# 03b3_USB_HUB.net
KiCad netlist of a schematic drawn in Altium Designer
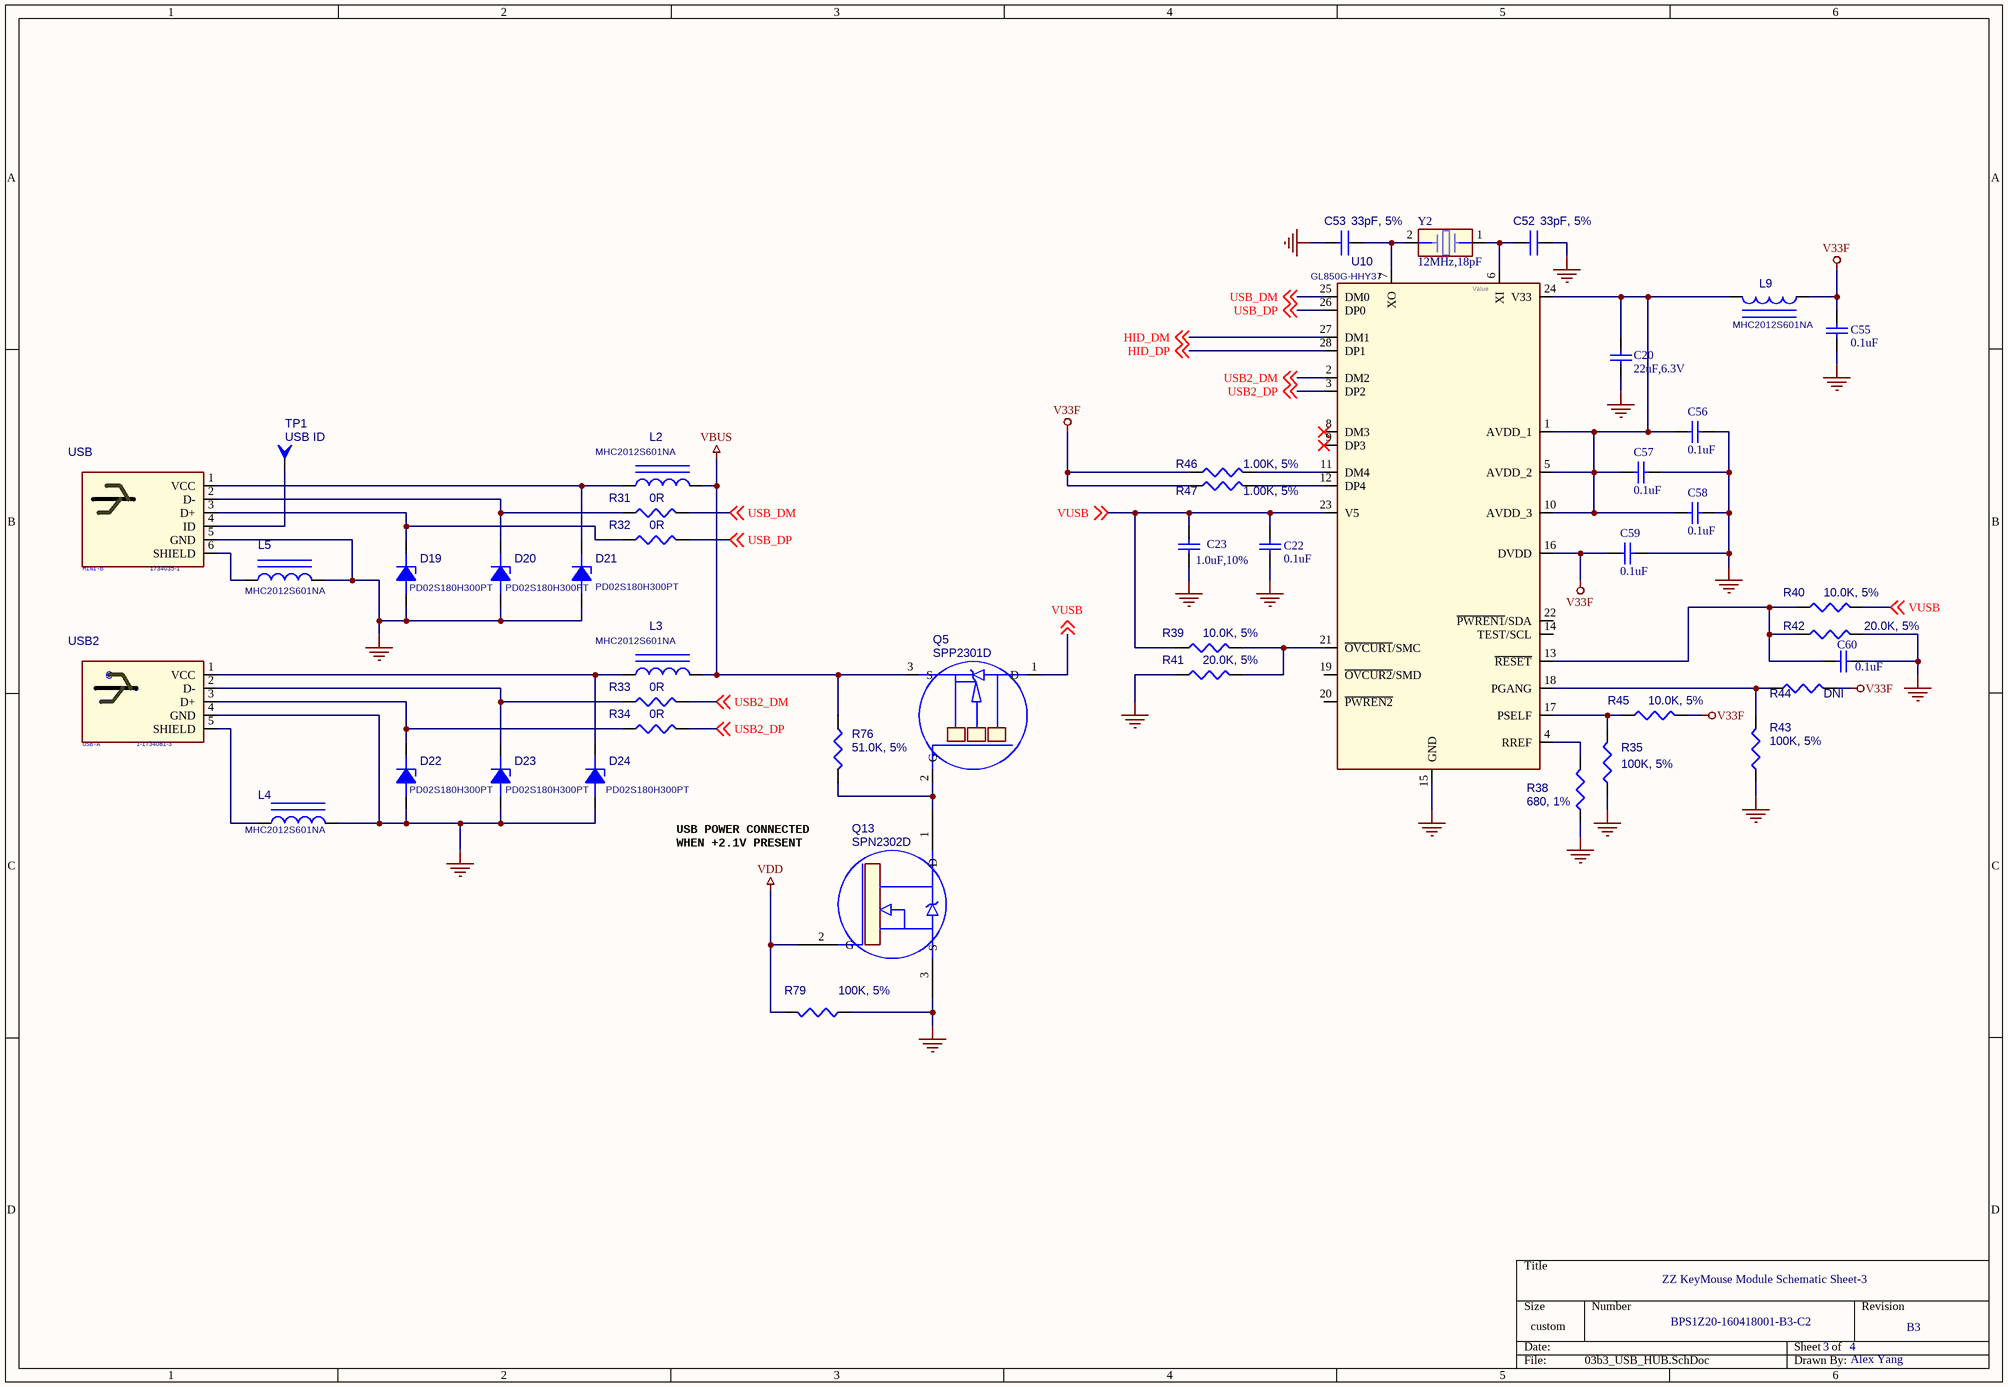
[diagram p0: 03b3_USB_HUB.SchDoc]

(export (version "E")
  (design (tool "Eeschema 10.0.6"))
  (components
    (comp (ref "C20")
      (value "22uF,6.3V")
      (footprint "MIN0805")
      (description "Capacitor")
      (libsource (lib "Miscellaneous Devices") (part "Cap"))
    )
    (comp (ref "C22")
      (value "0.1uF")
      (footprint "0603")
      (description "Capacitor")
      (libsource (lib "Miscellaneous Devices") (part "Cap"))
    )
    (comp (ref "C23")
      (value "1.0uF,10%")
      (footprint "0603")
      (description "Capacitor")
      (libsource (lib "Miscellaneous Devices") (part "Cap"))
    )
    (comp (ref "C52") (value "33pF, 5%") (footprint "0402") (libsource (lib "*") (part "CAPACITOR NON-POL")))
    (comp (ref "C53") (value "33pF, 5%") (footprint "0402") (libsource (lib "*") (part "CAPACITOR NON-POL")))
    (comp (ref "C55")
      (value "0.1uF")
      (footprint "0603")
      (description "Capacitor")
      (libsource (lib "Miscellaneous Devices") (part "Cap"))
    )
    (comp (ref "C56")
      (value "0.1uF")
      (footprint "0603")
      (description "Capacitor")
      (libsource (lib "Miscellaneous Devices") (part "Cap"))
    )
    (comp (ref "C57")
      (value "0.1uF")
      (footprint "0603")
      (description "Capacitor")
      (libsource (lib "Miscellaneous Devices") (part "Cap"))
    )
    (comp (ref "C58")
      (value "0.1uF")
      (footprint "0603")
      (description "Capacitor")
      (libsource (lib "Miscellaneous Devices") (part "Cap"))
    )
    (comp (ref "C59")
      (value "0.1uF")
      (footprint "0603")
      (description "Capacitor")
      (libsource (lib "Miscellaneous Devices") (part "Cap"))
    )
    (comp (ref "C60")
      (value "0.1uF")
      (footprint "0603")
      (description "Capacitor")
      (libsource (lib "Miscellaneous Devices") (part "Cap"))
    )
    (comp (ref "D19")
      (value "PD02S180H300PT")
      (footprint "ON_SEMI_ESD9L_SOD923")
      (libsource (lib "R MAIN") (part "DIODE BREAKDOWN"))
    )
    (comp (ref "D20")
      (value "PD02S180H300PT")
      (footprint "ON_SEMI_ESD9L_SOD923")
      (libsource (lib "R MAIN") (part "DIODE BREAKDOWN"))
    )
    (comp (ref "D21")
      (value "PD02S180H300PT")
      (footprint "ON_SEMI_ESD9L_SOD923")
      (libsource (lib "R MAIN") (part "DIODE BREAKDOWN"))
    )
    (comp (ref "D22")
      (value "PD02S180H300PT")
      (footprint "ON_SEMI_ESD9L_SOD923")
      (libsource (lib "R MAIN") (part "DIODE BREAKDOWN"))
    )
    (comp (ref "D23")
      (value "PD02S180H300PT")
      (footprint "ON_SEMI_ESD9L_SOD923")
      (libsource (lib "R MAIN") (part "DIODE BREAKDOWN"))
    )
    (comp (ref "D24")
      (value "PD02S180H300PT")
      (footprint "ON_SEMI_ESD9L_SOD923")
      (libsource (lib "R MAIN") (part "DIODE BREAKDOWN"))
    )
    (comp (ref "L2")
      (value "MHC2012S601NA")
      (footprint "RESC2012X70")
      (libsource (lib "*") (part "INDUCTOR IRON"))
    )
    (comp (ref "L3")
      (value "MHC2012S601NA")
      (footprint "RESC2012X70")
      (libsource (lib "*") (part "INDUCTOR IRON"))
    )
    (comp (ref "L4")
      (value "MHC2012S601NA")
      (footprint "RESC2012X70")
      (libsource (lib "*") (part "INDUCTOR IRON"))
    )
    (comp (ref "L5")
      (value "MHC2012S601NA")
      (footprint "RESC2012X70")
      (libsource (lib "*") (part "INDUCTOR IRON"))
    )
    (comp (ref "L9")
      (value "MHC2012S601NA")
      (footprint "RESC2012X70")
      (libsource (lib "*") (part "INDUCTOR IRON"))
    )
    (comp (ref "Q5") (value "SPP2301D") (footprint "SOT23") (libsource (lib "R MAIN") (part "AO3435")))
    (comp (ref "Q13") (value "SPN2302D") (footprint "SOT23") (libsource (lib "L MAIN") (part "AO3416")))
    (comp (ref "R31") (value "0R") (footprint "0402") (libsource (lib "*") (part "R")))
    (comp (ref "R32") (value "0R") (footprint "0402") (libsource (lib "*") (part "R")))
    (comp (ref "R33") (value "0R") (footprint "0402") (libsource (lib "*") (part "R")))
    (comp (ref "R34") (value "0R") (footprint "0402") (libsource (lib "*") (part "R")))
    (comp (ref "R35") (value "100K, 5%") (footprint "0402") (libsource (lib "*") (part "R")))
    (comp (ref "R38") (value "680, 1%") (footprint "0402") (libsource (lib "*") (part "R")))
    (comp (ref "R39") (value "10.0K, 5%") (footprint "0402") (libsource (lib "*") (part "R")))
    (comp (ref "R40") (value "10.0K, 5%") (footprint "0402") (libsource (lib "*") (part "R")))
    (comp (ref "R41") (value "20.0K, 5%") (footprint "0402") (libsource (lib "*") (part "R")))
    (comp (ref "R42") (value "20.0K, 5%") (footprint "0402") (libsource (lib "*") (part "R")))
    (comp (ref "R43") (value "100K, 5%") (footprint "0402") (libsource (lib "*") (part "R")))
    (comp (ref "R44") (value "DNI") (footprint "0402") (libsource (lib "*") (part "R")))
    (comp (ref "R45") (value "10.0K, 5%") (footprint "0402") (libsource (lib "*") (part "R")))
    (comp (ref "R46") (value "1.00K, 5%") (footprint "0402") (libsource (lib "*") (part "R")))
    (comp (ref "R47") (value "1.00K, 5%") (footprint "0402") (libsource (lib "*") (part "R")))
    (comp (ref "R76") (value "51.0K, 5%") (footprint "0402") (libsource (lib "*") (part "R")))
    (comp (ref "R79") (value "100K, 5%") (footprint "0402") (libsource (lib "*") (part "R")))
    (comp (ref "TP1") (value "USB ID") (footprint "TP1.5MM") (libsource (lib "*") (part "T POINT A")))
    (comp (ref "U10")
      (value "GL850G-HHY37")
      (footprint "SSOP28")
      (libsource (lib "*") (part "GL850G-HHY37_0"))
    )
    (comp (ref "USB")
      (value "1734035-1")
      (footprint "MINI-B_TE_1734035-1")
      (libsource (lib "L MAIN") (part "USB-MINI-B_0"))
    )
    (comp (ref "USB2")
      (value "1-1734081-3")
      (footprint "TE_1-1734081-3")
      (libsource (lib "L MAIN") (part "USB-A_1"))
    )
    (comp (ref "Y2")
      (value "12MHz,18pF")
      (footprint "TXC_HC-49S")
      (description "XTAL_CS10-25.000,18PF")
      (fields (field (name "FREQUENCY") "Value"))
      (libsource (lib "L MAIN_Library") (part "XTAL-25MHz_0"))
    )
  )
  (nets
    (net (code "1") (name "GND") (class "Default")
      (node (ref "C20") (pin "2") (pinfunction "2_2") (pintype "passive"))
      (node (ref "C22") (pin "1") (pinfunction "1_1") (pintype "passive"))
      (node (ref "C23") (pin "1") (pinfunction "1_1") (pintype "passive"))
      (node (ref "C52") (pin "1") (pinfunction "1_1") (pintype "passive"))
      (node (ref "C53") (pin "2") (pinfunction "2_2") (pintype "passive"))
      (node (ref "C55") (pin "1") (pinfunction "1_1") (pintype "passive"))
      (node (ref "C56") (pin "2") (pinfunction "2_2") (pintype "passive"))
      (node (ref "C57") (pin "2") (pinfunction "2_2") (pintype "passive"))
      (node (ref "C58") (pin "2") (pinfunction "2_2") (pintype "passive"))
      (node (ref "C59") (pin "2") (pinfunction "2_2") (pintype "passive"))
      (node (ref "C60") (pin "1") (pinfunction "1_1") (pintype "passive"))
      (node (ref "D19") (pin "A") (pinfunction "ANODE_A") (pintype "passive"))
      (node (ref "D20") (pin "A") (pinfunction "ANODE_A") (pintype "passive"))
      (node (ref "D21") (pin "A") (pinfunction "ANODE_A") (pintype "passive"))
      (node (ref "D22") (pin "A") (pinfunction "ANODE_A") (pintype "passive"))
      (node (ref "D23") (pin "A") (pinfunction "ANODE_A") (pintype "passive"))
      (node (ref "D24") (pin "A") (pinfunction "ANODE_A") (pintype "passive"))
      (node (ref "L4") (pin "2") (pinfunction "2_2") (pintype "passive"))
      (node (ref "L5") (pin "2") (pinfunction "2_2") (pintype "passive"))
      (node (ref "Q13") (pin "3") (pinfunction "S_3") (pintype "passive"))
      (node (ref "R35") (pin "1") (pinfunction "1_1") (pintype "passive"))
      (node (ref "R38") (pin "2") (pinfunction "2_2") (pintype "passive"))
      (node (ref "R41") (pin "1") (pinfunction "1_1") (pintype "passive"))
      (node (ref "R42") (pin "2") (pinfunction "2_2") (pintype "passive"))
      (node (ref "R43") (pin "1") (pinfunction "1_1") (pintype "passive"))
      (node (ref "R79") (pin "1") (pinfunction "1_1") (pintype "passive"))
      (node (ref "U10") (pin "15") (pinfunction "GND_15") (pintype "passive"))
      (node (ref "USB") (pin "5") (pinfunction "GND_5") (pintype "passive"))
      (node (ref "USB2") (pin "4") (pinfunction "GND_4") (pintype "passive"))
    )
    (net (code "2") (name "HID_DM") (class "Default")
      (node (ref "U10") (pin "27") (pinfunction "DM1_27") (pintype "passive"))
    )
    (net (code "3") (name "HID_DP") (class "Default")
      (node (ref "U10") (pin "28") (pinfunction "DP1_28") (pintype "passive"))
    )
    (net (code "4") (name "Net-(D19-CATHODE)") (class "Default")
      (node (ref "D19") (pin "K") (pinfunction "CATHODE_K") (pintype "passive"))
      (node (ref "R32") (pin "1") (pinfunction "1_1") (pintype "passive"))
      (node (ref "USB") (pin "3") (pinfunction "D+_3") (pintype "passive"))
    )
    (net (code "5") (name "Net-(D20-CATHODE)") (class "Default")
      (node (ref "D20") (pin "K") (pinfunction "CATHODE_K") (pintype "passive"))
      (node (ref "R31") (pin "1") (pinfunction "1_1") (pintype "passive"))
      (node (ref "USB") (pin "2") (pinfunction "D-_2") (pintype "passive"))
    )
    (net (code "6") (name "Net-(D21-CATHODE)") (class "Default")
      (node (ref "D21") (pin "K") (pinfunction "CATHODE_K") (pintype "passive"))
      (node (ref "L2") (pin "1") (pinfunction "1_1") (pintype "passive"))
      (node (ref "USB") (pin "1") (pinfunction "VCC_1") (pintype "passive"))
    )
    (net (code "7") (name "Net-(D22-CATHODE)") (class "Default")
      (node (ref "D22") (pin "K") (pinfunction "CATHODE_K") (pintype "passive"))
      (node (ref "R34") (pin "1") (pinfunction "1_1") (pintype "passive"))
      (node (ref "USB2") (pin "3") (pinfunction "D+_3") (pintype "passive"))
    )
    (net (code "8") (name "Net-(D23-CATHODE)") (class "Default")
      (node (ref "D23") (pin "K") (pinfunction "CATHODE_K") (pintype "passive"))
      (node (ref "R33") (pin "1") (pinfunction "1_1") (pintype "passive"))
      (node (ref "USB2") (pin "2") (pinfunction "D-_2") (pintype "passive"))
    )
    (net (code "9") (name "Net-(D24-CATHODE)") (class "Default")
      (node (ref "D24") (pin "K") (pinfunction "CATHODE_K") (pintype "passive"))
      (node (ref "L3") (pin "1") (pinfunction "1_1") (pintype "passive"))
      (node (ref "USB2") (pin "1") (pinfunction "VCC_1") (pintype "passive"))
    )
    (net (code "10") (name "Net-(Q13-D)") (class "Default")
      (node (ref "Q13") (pin "1") (pinfunction "D_1") (pintype "passive"))
      (node (ref "Q5") (pin "2") (pinfunction "G_2") (pintype "passive"))
      (node (ref "R76") (pin "2") (pinfunction "2_2") (pintype "passive"))
    )
    (net (code "11") (name "Net-(TP1-TP)") (class "Default")
      (node (ref "TP1") (pin "1") (pinfunction "TP_1") (pintype "passive"))
      (node (ref "USB") (pin "4") (pinfunction "ID_4") (pintype "passive"))
    )
    (net (code "12") (name "Net-(U10-AVDD_1)") (class "Default")
      (node (ref "C20") (pin "1") (pinfunction "1_1") (pintype "passive"))
      (node (ref "C56") (pin "1") (pinfunction "1_1") (pintype "passive"))
      (node (ref "C57") (pin "1") (pinfunction "1_1") (pintype "passive"))
      (node (ref "C58") (pin "1") (pinfunction "1_1") (pintype "passive"))
      (node (ref "L9") (pin "2") (pinfunction "2_2") (pintype "passive"))
      (node (ref "U10") (pin "1") (pinfunction "AVDD_1_1") (pintype "passive"))
      (node (ref "U10") (pin "10") (pinfunction "AVDD_3_10") (pintype "passive"))
      (node (ref "U10") (pin "24") (pinfunction "V33_24") (pintype "passive"))
      (node (ref "U10") (pin "5") (pinfunction "AVDD_2_5") (pintype "passive"))
    )
    (net (code "13") (name "Net-(U10-DM4)") (class "Default")
      (node (ref "R46") (pin "2") (pinfunction "2_2") (pintype "passive"))
      (node (ref "U10") (pin "11") (pinfunction "DM4_11") (pintype "passive"))
    )
    (net (code "14") (name "Net-(U10-DP4)") (class "Default")
      (node (ref "R47") (pin "2") (pinfunction "2_2") (pintype "passive"))
      (node (ref "U10") (pin "12") (pinfunction "DP4_12") (pintype "passive"))
    )
    (net (code "15") (name "Net-(U10-PGANG)") (class "Default")
      (node (ref "R43") (pin "2") (pinfunction "2_2") (pintype "passive"))
      (node (ref "R44") (pin "1") (pinfunction "1_1") (pintype "passive"))
      (node (ref "U10") (pin "18") (pinfunction "PGANG_18") (pintype "passive"))
    )
    (net (code "16") (name "Net-(U10-PSELF)") (class "Default")
      (node (ref "R35") (pin "2") (pinfunction "2_2") (pintype "passive"))
      (node (ref "R45") (pin "1") (pinfunction "1_1") (pintype "passive"))
      (node (ref "U10") (pin "17") (pinfunction "PSELF_17") (pintype "passive"))
    )
    (net (code "17") (name "Net-(U10-RREF)") (class "Default")
      (node (ref "R38") (pin "1") (pinfunction "1_1") (pintype "passive"))
      (node (ref "U10") (pin "4") (pinfunction "RREF_4") (pintype "passive"))
    )
    (net (code "18") (name "Net-(U10-XI)") (class "Default")
      (node (ref "C52") (pin "2") (pinfunction "2_2") (pintype "passive"))
      (node (ref "U10") (pin "6") (pinfunction "XI_6") (pintype "passive"))
      (node (ref "Y2") (pin "1") (pinfunction "1_1") (pintype "passive"))
    )
    (net (code "19") (name "Net-(U10-XO)") (class "Default")
      (node (ref "C53") (pin "1") (pinfunction "1_1") (pintype "passive"))
      (node (ref "U10") (pin "7") (pinfunction "XO_7") (pintype "passive"))
      (node (ref "Y2") (pin "2") (pinfunction "2_2") (pintype "passive"))
    )
    (net (code "20") (name "Net-(U10-~{OVCUR1}{slash}SMC)") (class "Default")
      (node (ref "R39") (pin "2") (pinfunction "2_2") (pintype "passive"))
      (node (ref "R41") (pin "2") (pinfunction "2_2") (pintype "passive"))
      (node (ref "U10") (pin "21") (pinfunction "~{OVCUR1}/SMC_21") (pintype "passive"))
    )
    (net (code "21") (name "Net-(U10-~{RESET})") (class "Default")
      (node (ref "C60") (pin "2") (pinfunction "2_2") (pintype "passive"))
      (node (ref "R40") (pin "1") (pinfunction "1_1") (pintype "passive"))
      (node (ref "R42") (pin "1") (pinfunction "1_1") (pintype "passive"))
      (node (ref "U10") (pin "13") (pinfunction "~{RESET}_13") (pintype "passive"))
    )
    (net (code "22") (name "Net-(USB-SHIELD)") (class "Default")
      (node (ref "L5") (pin "1") (pinfunction "1_1") (pintype "passive"))
      (node (ref "USB") (pin "6") (pinfunction "SHIELD_6") (pintype "passive"))
    )
    (net (code "23") (name "Net-(USB2-SHIELD)") (class "Default")
      (node (ref "L4") (pin "1") (pinfunction "1_1") (pintype "passive"))
      (node (ref "USB2") (pin "5") (pinfunction "SHIELD_5") (pintype "passive"))
    )
    (net (code "24") (name "USB2_DM") (class "Default")
      (node (ref "R33") (pin "2") (pinfunction "2_2") (pintype "passive"))
      (node (ref "U10") (pin "2") (pinfunction "DM2_2") (pintype "passive"))
    )
    (net (code "25") (name "USB2_DP") (class "Default")
      (node (ref "R34") (pin "2") (pinfunction "2_2") (pintype "passive"))
      (node (ref "U10") (pin "3") (pinfunction "DP2_3") (pintype "passive"))
    )
    (net (code "26") (name "USB_DM") (class "Default")
      (node (ref "R31") (pin "2") (pinfunction "2_2") (pintype "passive"))
      (node (ref "U10") (pin "25") (pinfunction "DM0_25") (pintype "passive"))
    )
    (net (code "27") (name "USB_DP") (class "Default")
      (node (ref "R32") (pin "2") (pinfunction "2_2") (pintype "passive"))
      (node (ref "U10") (pin "26") (pinfunction "DP0_26") (pintype "passive"))
    )
    (net (code "28") (name "V33F") (class "Default")
      (node (ref "C55") (pin "2") (pinfunction "2_2") (pintype "passive"))
      (node (ref "C59") (pin "1") (pinfunction "1_1") (pintype "passive"))
      (node (ref "L9") (pin "1") (pinfunction "1_1") (pintype "passive"))
      (node (ref "R44") (pin "2") (pinfunction "2_2") (pintype "passive"))
      (node (ref "R45") (pin "2") (pinfunction "2_2") (pintype "passive"))
      (node (ref "R46") (pin "1") (pinfunction "1_1") (pintype "passive"))
      (node (ref "R47") (pin "1") (pinfunction "1_1") (pintype "passive"))
      (node (ref "U10") (pin "16") (pinfunction "DVDD_16") (pintype "passive"))
    )
    (net (code "29") (name "VBUS") (class "Default")
      (node (ref "L2") (pin "2") (pinfunction "2_2") (pintype "passive"))
      (node (ref "L3") (pin "2") (pinfunction "2_2") (pintype "passive"))
      (node (ref "Q5") (pin "3") (pinfunction "S_3") (pintype "passive"))
      (node (ref "R76") (pin "1") (pinfunction "1_1") (pintype "passive"))
    )
    (net (code "30") (name "VDD") (class "Default")
      (node (ref "Q13") (pin "2") (pinfunction "G_2") (pintype "passive"))
      (node (ref "R79") (pin "2") (pinfunction "2_2") (pintype "passive"))
    )
    (net (code "31") (name "VUSB") (class "Default")
      (node (ref "C22") (pin "2") (pinfunction "2_2") (pintype "passive"))
      (node (ref "C23") (pin "2") (pinfunction "2_2") (pintype "passive"))
      (node (ref "Q5") (pin "1") (pinfunction "D_1") (pintype "passive"))
      (node (ref "R39") (pin "1") (pinfunction "1_1") (pintype "passive"))
      (node (ref "R40") (pin "2") (pinfunction "2_2") (pintype "passive"))
      (node (ref "U10") (pin "23") (pinfunction "V5_23") (pintype "passive"))
    )
    (net (code "32") (name "unconnected-(U10-DM3-Pad8)") (class "Default")
      (node (ref "U10") (pin "8") (pinfunction "DM3_8") (pintype "passive+no_connect"))
    )
    (net (code "33") (name "unconnected-(U10-DP3-Pad9)") (class "Default")
      (node (ref "U10") (pin "9") (pinfunction "DP3_9") (pintype "passive+no_connect"))
    )
    (net (code "34") (name "unconnected-(U10-TEST{slash}SCL-Pad14)") (class "Default")
      (node (ref "U10") (pin "14") (pinfunction "TEST/SCL_14") (pintype "passive"))
    )
    (net (code "35") (name "unconnected-(U10-~{OVCUR2}{slash}SMD-Pad19)") (class "Default")
      (node (ref "U10") (pin "19") (pinfunction "~{OVCUR2}/SMD_19") (pintype "passive"))
    )
    (net (code "36") (name "unconnected-(U10-~{PWREN1}{slash}SDA-Pad22)") (class "Default")
      (node (ref "U10") (pin "22") (pinfunction "~{PWREN1}/SDA_22") (pintype "passive"))
    )
    (net (code "37") (name "unconnected-(U10-~{PWREN2}-Pad20)") (class "Default")
      (node (ref "U10") (pin "20") (pinfunction "~{PWREN2}_20") (pintype "passive"))
    )
  )
)
